# esp32wrom.net
KiCad netlist of a schematic drawn in Altium Designer
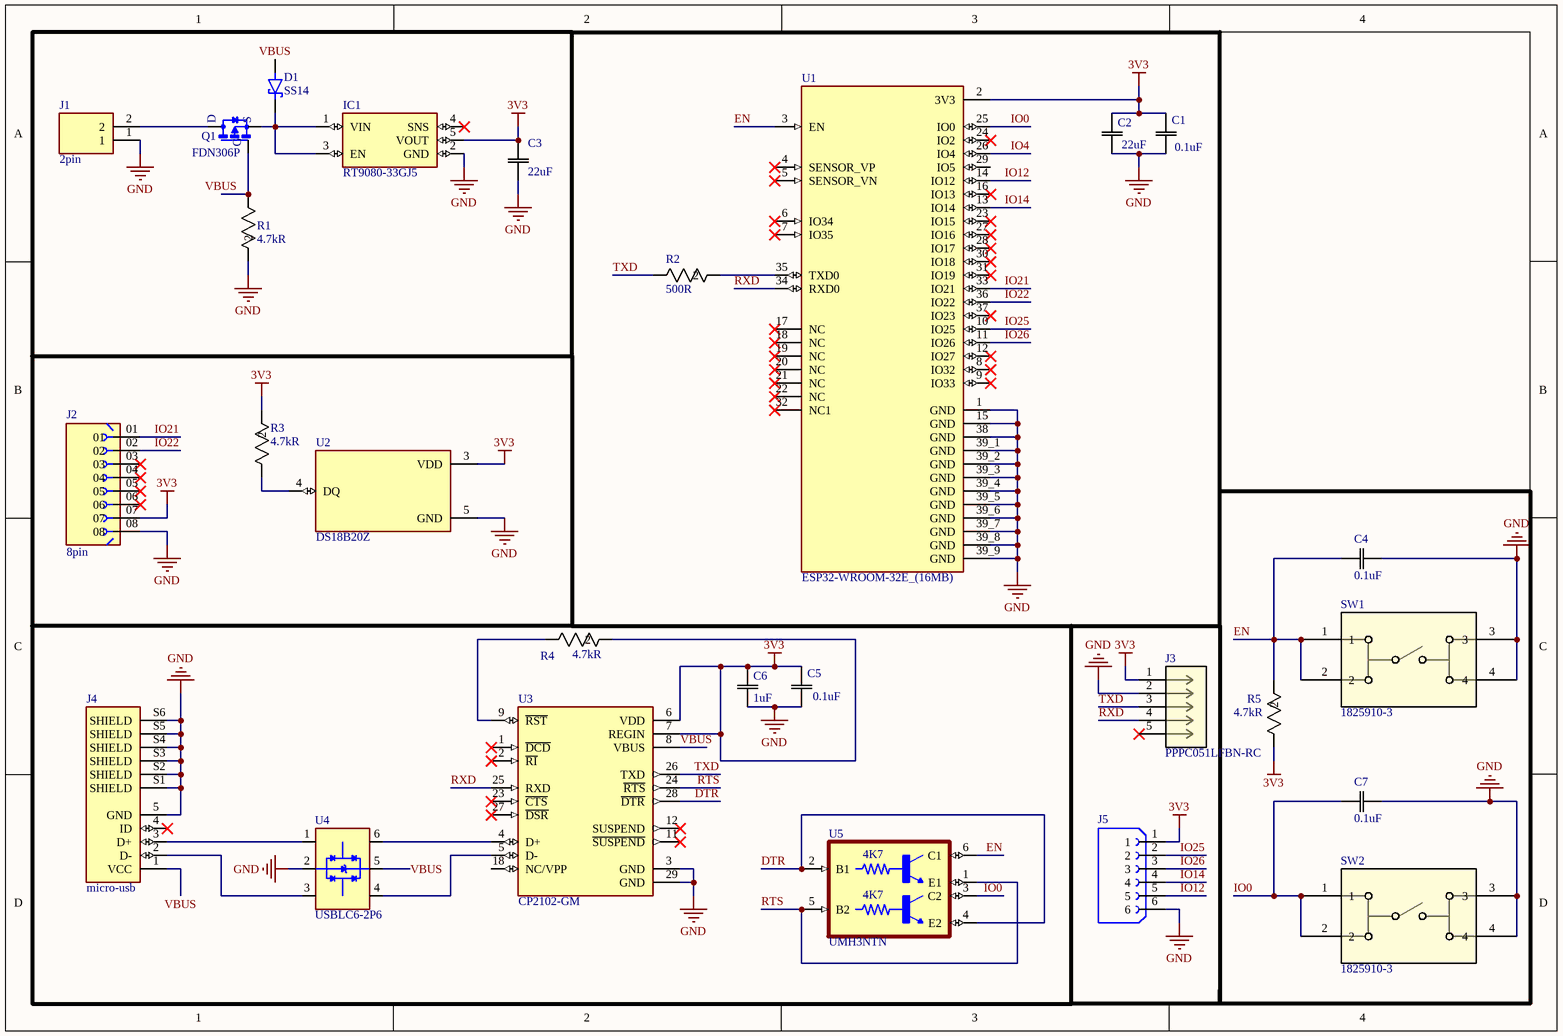
[diagram p0: esp32wrom.SchDoc]

(export (version "E")
  (design (tool "Eeschema 10.0.6"))
  (components
    (comp (ref "C1")
      (value "0.1uF")
      (footprint "0603_AVX")
      (description "Description")
      (fields
        (field (name "MANUFACTURER_PART_NUMBER") "0603YC683KAT2A")
        (field (name "COPYRIGHT") "Copyright (C) 2025 Ultra Librarian. All rights reserved.")
      )
      (libsource (lib "capacitor") (part "0603"))
    )
    (comp (ref "C2")
      (value "22uF")
      (footprint "0603_AVX")
      (description "Description")
      (fields
        (field (name "MANUFACTURER_PART_NUMBER") "0603YC683KAT2A")
        (field (name "COPYRIGHT") "Copyright (C) 2025 Ultra Librarian. All rights reserved.")
      )
      (libsource (lib "capacitor") (part "0603"))
    )
    (comp (ref "C3")
      (value "22uF")
      (footprint "0603_AVX")
      (description "Description")
      (fields
        (field (name "MANUFACTURER_PART_NUMBER") "0603YC683KAT2A")
        (field (name "COPYRIGHT") "Copyright (C) 2025 Ultra Librarian. All rights reserved.")
      )
      (libsource (lib "capacitor") (part "0603"))
    )
    (comp (ref "C4")
      (value "0.1uF")
      (footprint "0603_AVX")
      (description "Description")
      (fields
        (field (name "MANUFACTURER_PART_NUMBER") "0603YC683KAT2A")
        (field (name "COPYRIGHT") "Copyright (C) 2025 Ultra Librarian. All rights reserved.")
      )
      (libsource (lib "capacitor") (part "0603"))
    )
    (comp (ref "C5")
      (value "0.1uF")
      (footprint "0603_AVX")
      (description "Description")
      (fields
        (field (name "MANUFACTURER_PART_NUMBER") "0603YC683KAT2A")
        (field (name "COPYRIGHT") "Copyright (C) 2025 Ultra Librarian. All rights reserved.")
      )
      (libsource (lib "capacitor") (part "0603"))
    )
    (comp (ref "C6")
      (value "1uF")
      (footprint "0603_AVX")
      (description "Description")
      (fields
        (field (name "MANUFACTURER_PART_NUMBER") "0603YC683KAT2A")
        (field (name "COPYRIGHT") "Copyright (C) 2025 Ultra Librarian. All rights reserved.")
      )
      (libsource (lib "capacitor") (part "0603"))
    )
    (comp (ref "C7")
      (value "0.1uF")
      (footprint "0603_AVX")
      (description "Description")
      (fields
        (field (name "MANUFACTURER_PART_NUMBER") "0603YC683KAT2A")
        (field (name "COPYRIGHT") "Copyright (C) 2025 Ultra Librarian. All rights reserved.")
      )
      (libsource (lib "capacitor") (part "0603"))
    )
    (comp (ref "D1")
      (value "SS14")
      (footprint "DIOM4325X250N")
      (description "1A, 40V, Schottky Rectifier")
      (fields (field (name "MF") "Taiwan Semiconductor"))
      (libsource (lib "stm32_Wrom") (part "SS14"))
    )
    (comp (ref "IC1")
      (value "RT9080-33GJ5")
      (footprint "SOT94P280X100-5N")
      (description "Linear Voltage Regulator IC Positive Fixed 1 Output 600mA TSOT-23-5")
      (fields (field (name "MF") "Richtek USA"))
      (libsource (lib "stm32_Wrom") (part "RT9080-33GJ5"))
    )
    (comp (ref "J1")
      (value "2pin")
      (footprint "JST_S2B-PH-K-S(LF)(SN)")
      (description "Connector Header Through Hole, Right Angle 2 position")
      (fields (field (name "MP") "S2B-PH-K-S(LF)(SN)") (field (name "MF") "JST Sales America Inc."))
      (libsource (lib "stm32_Wrom") (part "2pin"))
    )
    (comp (ref "J2")
      (value "8pin")
      (footprint "AMPHENOL_76308-108LF")
      (fields (field (name "MP") "76308-108LF") (field (name "MF") "Amphenol"))
      (libsource (lib "stm32_Wrom") (part "8pin"))
    )
    (comp (ref "J3")
      (value "PPPC051LFBN-RC")
      (footprint "CONN_PPPC051LFBN-RC_SUL")
      (description "Description")
      (fields (field (name "COPYRIGHT") "Copyright (C) 2025 Ultra Librarian. All rights reserved."))
      (libsource (lib "stm32_Wrom") (part "5pin"))
    )
    (comp (ref "J4")
      (value "micro-usb")
      (footprint "AMPHENOL_10118192-0002LF")
      (description "Micro USB 2.0, Input Output Connectors, B TYPE RECEPTACLE without flange")
      (fields (field (name "MF") "Amphenol ICC") (field (name "MP") "10118192-0002LF"))
      (libsource (lib "stm32_Wrom") (part "micro-usb"))
    )
    (comp (ref "J5")
      (value "6pin")
      (footprint "SULLINS_PPTC061LFBN-RC")
      (description "6 Position Total Single Row 2.54 mm Pitch Straight Female Header")
      (fields (field (name "MF") "Sullins Connector Solutions") (field (name "MP") "PPTC061LFBNRC"))
      (libsource (lib "stm32_Wrom") (part "6pin"))
    )
    (comp (ref "Q1")
      (value "FDN306P")
      (footprint "SSOT-3")
      (description "P-Channel 12V 2.6A (Ta) 500mW (Ta) Surface Mount SuperSOT-3")
      (fields (field (name "MF") "ON Semiconductor"))
      (libsource (lib "stm32_Wrom") (part "FDN306P"))
    )
    (comp (ref "R1")
      (value "4.7kR")
      (footprint "RC0603N_PAN")
      (description "No Description Available")
      (fields
        (field (name "MANUFACTURER_PART_NUMBER") "ERJ-3GEYJ6R8V")
        (field (name "COPYRIGHT") "Copyright (C) 2025 Ultra Librarian. All rights reserved.")
      )
      (libsource (lib "resistor") (part "0603"))
    )
    (comp (ref "R2")
      (value "500R")
      (footprint "RC0603N_PAN")
      (description "No Description Available")
      (fields
        (field (name "MANUFACTURER_PART_NUMBER") "ERJ-3GEYJ6R8V")
        (field (name "COPYRIGHT") "Copyright (C) 2025 Ultra Librarian. All rights reserved.")
      )
      (libsource (lib "resistor") (part "0603"))
    )
    (comp (ref "R3")
      (value "4.7kR")
      (footprint "RC0603N_PAN")
      (description "No Description Available")
      (fields
        (field (name "MANUFACTURER_PART_NUMBER") "ERJ-3GEYJ6R8V")
        (field (name "COPYRIGHT") "Copyright (C) 2025 Ultra Librarian. All rights reserved.")
      )
      (libsource (lib "resistor") (part "0603"))
    )
    (comp (ref "R4")
      (value "4.7kR")
      (footprint "RC0603N_PAN")
      (description "No Description Available")
      (fields
        (field (name "MANUFACTURER_PART_NUMBER") "ERJ-3GEYJ6R8V")
        (field (name "COPYRIGHT") "Copyright (C) 2025 Ultra Librarian. All rights reserved.")
      )
      (libsource (lib "resistor") (part "0603"))
    )
    (comp (ref "R5")
      (value "4.7kR")
      (footprint "RC0603N_PAN")
      (description "No Description Available")
      (fields
        (field (name "MANUFACTURER_PART_NUMBER") "ERJ-3GEYJ6R8V")
        (field (name "COPYRIGHT") "Copyright (C) 2025 Ultra Librarian. All rights reserved.")
      )
      (libsource (lib "resistor") (part "0603"))
    )
    (comp (ref "SW1")
      (value "1825910-3")
      (footprint "SW4_1825910-A_TEC")
      (description "FSM2JAH=6MM TACT SWITCH, HIGH TEMP")
      (fields (field (name "COPYRIGHT") "Copyright (C) 2025 Ultra Librarian. All rights reserved."))
      (libsource (lib "stm32_Wrom") (part "1825910-3"))
    )
    (comp (ref "SW2")
      (value "1825910-3")
      (footprint "SW4_1825910-A_TEC")
      (description "FSM2JAH=6MM TACT SWITCH, HIGH TEMP")
      (fields (field (name "COPYRIGHT") "Copyright (C) 2025 Ultra Librarian. All rights reserved."))
      (libsource (lib "stm32_Wrom") (part "1825910-3"))
    )
    (comp (ref "U1")
      (value "ESP32-WROOM-32E_(16MB)")
      (footprint "XCVR_ESP32-WROOM-32E_(16MB)")
      (fields (field (name "MP") "ESP32-WROOM-32E (16MB)") (field (name "MF") "Espressif Systems"))
      (libsource (lib "stm32_Wrom") (part "ESP32-WROOM-32E_(16MB)"))
    )
    (comp (ref "U2")
      (value "DS18B20Z")
      (footprint "SOIC127P600X175-8N")
      (description "Programmable Resolution 1-Wire Digital Thermometer")
      (fields (field (name "MF") "Analog Devices") (field (name "MP") "DS18B20Z+T&amp;R"))
      (libsource (lib "stm32_Wrom") (part "DS18B20Z"))
    )
    (comp (ref "U3")
      (value "CP2102-GM")
      (footprint "QFN50P500X500X100-29N")
      (description "USB Bridge, USB to UART USB 2.0 UART Interface 28-QFN (5x5)")
      (fields (field (name "MF") "Silicon Labs"))
      (libsource (lib "stm32_Wrom") (part "CP2102-GM"))
    )
    (comp (ref "U4")
      (value "USBLC6-2P6")
      (footprint "SOT50P160X60-6N")
      (description "17V Clamp 5A (8/20Âµs) Ipp Tvs Diode Surface Mount SOT-666")
      (fields (field (name "MF") "STMicroelectronics"))
      (libsource (lib "stm32_Wrom") (part "USBLC6-2P6"))
    )
    (comp (ref "U5")
      (value "UMH3NTN")
      (footprint "SOP65P210X100-6N")
      (fields (field (name "MF") "Rohm"))
      (libsource (lib "stm32_Wrom") (part "UMH3NTN"))
    )
  )
  (nets
    (net (code "1") (name "/DTR") (class "Default")
      (node (ref "U3") (pin "28") (pinfunction "~{DTR}_28") (pintype "output"))
      (node (ref "U5") (pin "2") (pinfunction "B1_2") (pintype "input"))
      (node (ref "U5") (pin "4") (pinfunction "E2_4") (pintype "bidirectional"))
    )
    (net (code "2") (name "/EN") (class "Default")
      (node (ref "C4") (pin "2") (pinfunction "2_2") (pintype "passive"))
      (node (ref "R5") (pin "2") (pinfunction "2_2") (pintype "passive"))
      (node (ref "SW1") (pin "1") (pinfunction "1_1") (pintype "passive"))
      (node (ref "SW1") (pin "2") (pinfunction "2_2") (pintype "passive"))
      (node (ref "U1") (pin "3") (pinfunction "EN_3") (pintype "input"))
      (node (ref "U5") (pin "6") (pinfunction "C1_6") (pintype "bidirectional"))
    )
    (net (code "3") (name "/IO0") (class "Default")
      (node (ref "C7") (pin "2") (pinfunction "2_2") (pintype "passive"))
      (node (ref "SW2") (pin "1") (pinfunction "1_1") (pintype "passive"))
      (node (ref "SW2") (pin "2") (pinfunction "2_2") (pintype "passive"))
      (node (ref "U1") (pin "25") (pinfunction "IO0_25") (pintype "bidirectional"))
      (node (ref "U5") (pin "3") (pinfunction "C2_3") (pintype "bidirectional"))
    )
    (net (code "4") (name "/IO4") (class "Default")
      (node (ref "U1") (pin "26") (pinfunction "IO4_26") (pintype "bidirectional"))
    )
    (net (code "5") (name "/IO12") (class "Default")
      (node (ref "J5") (pin "5") (pinfunction "5_5") (pintype "passive"))
      (node (ref "U1") (pin "14") (pinfunction "IO12_14") (pintype "bidirectional"))
    )
    (net (code "6") (name "/IO14") (class "Default")
      (node (ref "J5") (pin "4") (pinfunction "4_4") (pintype "passive"))
      (node (ref "U1") (pin "13") (pinfunction "IO14_13") (pintype "bidirectional"))
    )
    (net (code "7") (name "/IO21") (class "Default")
      (node (ref "J2") (pin "01") (pinfunction "01_01") (pintype "passive"))
      (node (ref "U1") (pin "33") (pinfunction "IO21_33") (pintype "bidirectional"))
    )
    (net (code "8") (name "/IO22") (class "Default")
      (node (ref "J2") (pin "02") (pinfunction "02_02") (pintype "passive"))
      (node (ref "U1") (pin "36") (pinfunction "IO22_36") (pintype "bidirectional"))
    )
    (net (code "9") (name "/IO25") (class "Default")
      (node (ref "J5") (pin "2") (pinfunction "2_2") (pintype "passive"))
      (node (ref "U1") (pin "10") (pinfunction "IO25_10") (pintype "bidirectional"))
    )
    (net (code "10") (name "/IO26") (class "Default")
      (node (ref "J5") (pin "3") (pinfunction "3_3") (pintype "passive"))
      (node (ref "U1") (pin "11") (pinfunction "IO26_11") (pintype "bidirectional"))
    )
    (net (code "11") (name "/RTS") (class "Default")
      (node (ref "U3") (pin "24") (pinfunction "~{RTS}_24") (pintype "output"))
      (node (ref "U5") (pin "1") (pinfunction "E1_1") (pintype "bidirectional"))
      (node (ref "U5") (pin "5") (pinfunction "B2_5") (pintype "input"))
    )
    (net (code "12") (name "/RXD") (class "Default")
      (node (ref "J3") (pin "4") (pinfunction "4_4") (pintype "passive"))
      (node (ref "U1") (pin "34") (pinfunction "RXD0_34") (pintype "bidirectional"))
      (node (ref "U3") (pin "25") (pinfunction "RXD_25") (pintype "input"))
    )
    (net (code "13") (name "/TXD") (class "Default")
      (node (ref "J3") (pin "3") (pinfunction "3_3") (pintype "passive"))
      (node (ref "R2") (pin "1") (pinfunction "1_1") (pintype "passive"))
      (node (ref "U3") (pin "26") (pinfunction "TXD_26") (pintype "output"))
    )
    (net (code "14") (name "/VBUS") (class "Default")
      (node (ref "D1") (pin "A") (pinfunction "A_A") (pintype "passive"))
      (node (ref "J4") (pin "1") (pinfunction "VCC_1") (pintype "power_in"))
      (node (ref "Q1") (pin "1") (pinfunction "G_1") (pintype "passive"))
      (node (ref "R1") (pin "1") (pinfunction "1_1") (pintype "passive"))
      (node (ref "U3") (pin "8") (pinfunction "VBUS_8") (pintype "power_in"))
      (node (ref "U4") (pin "5") (pinfunction "VBUS_5") (pintype "power_in"))
    )
    (net (code "15") (name "3V3") (class "Default")
      (node (ref "C1") (pin "2") (pinfunction "2_2") (pintype "passive"))
      (node (ref "C2") (pin "2") (pinfunction "2_2") (pintype "passive"))
      (node (ref "C3") (pin "2") (pinfunction "2_2") (pintype "passive"))
      (node (ref "C5") (pin "2") (pinfunction "2_2") (pintype "passive"))
      (node (ref "C6") (pin "2") (pinfunction "2_2") (pintype "passive"))
      (node (ref "IC1") (pin "5") (pinfunction "VOUT_5") (pintype "bidirectional"))
      (node (ref "J2") (pin "07") (pinfunction "07_07") (pintype "passive"))
      (node (ref "J3") (pin "1") (pinfunction "1_1") (pintype "passive"))
      (node (ref "J5") (pin "1") (pinfunction "1_1") (pintype "passive"))
      (node (ref "R3") (pin "2") (pinfunction "2_2") (pintype "passive"))
      (node (ref "R4") (pin "2") (pinfunction "2_2") (pintype "passive"))
      (node (ref "R5") (pin "1") (pinfunction "1_1") (pintype "passive"))
      (node (ref "U1") (pin "2") (pinfunction "3V3_2") (pintype "power_in"))
      (node (ref "U2") (pin "3") (pinfunction "VDD_3") (pintype "power_in"))
      (node (ref "U3") (pin "6") (pinfunction "VDD_6") (pintype "power_in"))
      (node (ref "U3") (pin "7") (pinfunction "REGIN_7") (pintype "power_in"))
    )
    (net (code "16") (name "GND") (class "Default")
      (node (ref "C1") (pin "1") (pinfunction "1_1") (pintype "passive"))
      (node (ref "C2") (pin "1") (pinfunction "1_1") (pintype "passive"))
      (node (ref "C3") (pin "1") (pinfunction "1_1") (pintype "passive"))
      (node (ref "C4") (pin "1") (pinfunction "1_1") (pintype "passive"))
      (node (ref "C5") (pin "1") (pinfunction "1_1") (pintype "passive"))
      (node (ref "C6") (pin "1") (pinfunction "1_1") (pintype "passive"))
      (node (ref "C7") (pin "1") (pinfunction "1_1") (pintype "passive"))
      (node (ref "IC1") (pin "2") (pinfunction "GND_2") (pintype "bidirectional"))
      (node (ref "J1") (pin "1") (pinfunction "1_1") (pintype "passive"))
      (node (ref "J2") (pin "08") (pinfunction "08_08") (pintype "passive"))
      (node (ref "J3") (pin "2") (pinfunction "2_2") (pintype "passive"))
      (node (ref "J4") (pin "5") (pinfunction "GND_5") (pintype "power_in"))
      (node (ref "J4") (pin "S1") (pinfunction "SHIELD_S1") (pintype "passive"))
      (node (ref "J4") (pin "S2") (pinfunction "SHIELD_S2") (pintype "passive"))
      (node (ref "J4") (pin "S3") (pinfunction "SHIELD_S3") (pintype "passive"))
      (node (ref "J4") (pin "S4") (pinfunction "SHIELD_S4") (pintype "passive"))
      (node (ref "J4") (pin "S5") (pinfunction "SHIELD_S5") (pintype "passive"))
      (node (ref "J4") (pin "S6") (pinfunction "SHIELD_S6") (pintype "passive"))
      (node (ref "J5") (pin "6") (pinfunction "6_6") (pintype "passive"))
      (node (ref "R1") (pin "2") (pinfunction "2_2") (pintype "passive"))
      (node (ref "SW1") (pin "3") (pinfunction "3_3") (pintype "passive"))
      (node (ref "SW1") (pin "4") (pinfunction "4_4") (pintype "passive"))
      (node (ref "SW2") (pin "3") (pinfunction "3_3") (pintype "passive"))
      (node (ref "SW2") (pin "4") (pinfunction "4_4") (pintype "passive"))
      (node (ref "U1") (pin "1") (pinfunction "GND_1") (pintype "power_in"))
      (node (ref "U1") (pin "15") (pinfunction "GND_15") (pintype "power_in"))
      (node (ref "U1") (pin "38") (pinfunction "GND_38") (pintype "power_in"))
      (node (ref "U1") (pin "39_1") (pinfunction "GND_39_1") (pintype "power_in"))
      (node (ref "U1") (pin "39_2") (pinfunction "GND_39_2") (pintype "power_in"))
      (node (ref "U1") (pin "39_3") (pinfunction "GND_39_3") (pintype "power_in"))
      (node (ref "U1") (pin "39_4") (pinfunction "GND_39_4") (pintype "power_in"))
      (node (ref "U1") (pin "39_5") (pinfunction "GND_39_5") (pintype "power_in"))
      (node (ref "U1") (pin "39_6") (pinfunction "GND_39_6") (pintype "power_in"))
      (node (ref "U1") (pin "39_7") (pinfunction "GND_39_7") (pintype "power_in"))
      (node (ref "U1") (pin "39_8") (pinfunction "GND_39_8") (pintype "power_in"))
      (node (ref "U1") (pin "39_9") (pinfunction "GND_39_9") (pintype "power_in"))
      (node (ref "U2") (pin "5") (pinfunction "GND_5") (pintype "power_in"))
      (node (ref "U3") (pin "29") (pinfunction "GND_29") (pintype "power_in"))
      (node (ref "U3") (pin "3") (pinfunction "GND_3") (pintype "power_in"))
      (node (ref "U4") (pin "2") (pinfunction "GND_2") (pintype "power_in"))
    )
    (net (code "17") (name "Net-(D1-K)") (class "Default")
      (node (ref "D1") (pin "C") (pinfunction "K_C") (pintype "passive"))
      (node (ref "IC1") (pin "1") (pinfunction "VIN_1") (pintype "bidirectional"))
      (node (ref "IC1") (pin "3") (pinfunction "EN_3") (pintype "bidirectional"))
      (node (ref "Q1") (pin "2") (pinfunction "S_2") (pintype "passive"))
    )
    (net (code "18") (name "Net-(J4-D+)") (class "Default")
      (node (ref "J4") (pin "3") (pinfunction "D+_3") (pintype "bidirectional"))
      (node (ref "U4") (pin "1") (pinfunction "I/O1_1_1") (pintype "bidirectional"))
    )
    (net (code "19") (name "Net-(J4-D-)") (class "Default")
      (node (ref "J4") (pin "2") (pinfunction "D-_2") (pintype "bidirectional"))
      (node (ref "U4") (pin "3") (pinfunction "I/O2_1_3") (pintype "bidirectional"))
    )
    (net (code "20") (name "Net-(Q1-D)") (class "Default")
      (node (ref "J1") (pin "2") (pinfunction "2_2") (pintype "passive"))
      (node (ref "Q1") (pin "3") (pinfunction "D_3") (pintype "passive"))
    )
    (net (code "21") (name "Net-(U1-TXD0)") (class "Default")
      (node (ref "R2") (pin "2") (pinfunction "2_2") (pintype "passive"))
      (node (ref "U1") (pin "35") (pinfunction "TXD0_35") (pintype "bidirectional"))
    )
    (net (code "22") (name "Net-(U2-DQ)") (class "Default")
      (node (ref "R3") (pin "1") (pinfunction "1_1") (pintype "passive"))
      (node (ref "U2") (pin "4") (pinfunction "DQ_4") (pintype "bidirectional"))
    )
    (net (code "23") (name "Net-(U3-D+)") (class "Default")
      (node (ref "U3") (pin "4") (pinfunction "D+_4") (pintype "bidirectional"))
      (node (ref "U4") (pin "6") (pinfunction "I/O1_2_6") (pintype "bidirectional"))
    )
    (net (code "24") (name "Net-(U3-D-)") (class "Default")
      (node (ref "U3") (pin "5") (pinfunction "D-_5") (pintype "bidirectional"))
      (node (ref "U4") (pin "4") (pinfunction "I/O2_2_4") (pintype "bidirectional"))
    )
    (net (code "25") (name "Net-(U3-~{RST})") (class "Default")
      (node (ref "R4") (pin "1") (pinfunction "1_1") (pintype "passive"))
      (node (ref "U3") (pin "9") (pinfunction "~{RST}_9") (pintype "bidirectional"))
    )
    (net (code "26") (name "unconnected-(IC1-SNS-Pad4)") (class "Default")
      (node (ref "IC1") (pin "4") (pinfunction "SNS_4") (pintype "bidirectional+no_connect"))
    )
    (net (code "27") (name "unconnected-(J2-Pad03)") (class "Default")
      (node (ref "J2") (pin "03") (pinfunction "03_03") (pintype "passive+no_connect"))
    )
    (net (code "28") (name "unconnected-(J2-Pad04)") (class "Default")
      (node (ref "J2") (pin "04") (pinfunction "04_04") (pintype "passive+no_connect"))
    )
    (net (code "29") (name "unconnected-(J2-Pad05)") (class "Default")
      (node (ref "J2") (pin "05") (pinfunction "05_05") (pintype "passive+no_connect"))
    )
    (net (code "30") (name "unconnected-(J2-Pad06)") (class "Default")
      (node (ref "J2") (pin "06") (pinfunction "06_06") (pintype "passive+no_connect"))
    )
    (net (code "31") (name "unconnected-(J3-Pad5)") (class "Default")
      (node (ref "J3") (pin "5") (pinfunction "5_5") (pintype "passive+no_connect"))
    )
    (net (code "32") (name "unconnected-(J4-ID-Pad4)") (class "Default")
      (node (ref "J4") (pin "4") (pinfunction "ID_4") (pintype "bidirectional+no_connect"))
    )
    (net (code "33") (name "unconnected-(U1-IO2-Pad24)") (class "Default")
      (node (ref "U1") (pin "24") (pinfunction "IO2_24") (pintype "bidirectional+no_connect"))
    )
    (net (code "34") (name "unconnected-(U1-IO5-Pad29)") (class "Default")
      (node (ref "U1") (pin "29") (pinfunction "IO5_29") (pintype "bidirectional"))
    )
    (net (code "35") (name "unconnected-(U1-IO13-Pad16)") (class "Default")
      (node (ref "U1") (pin "16") (pinfunction "IO13_16") (pintype "bidirectional+no_connect"))
    )
    (net (code "36") (name "unconnected-(U1-IO15-Pad23)") (class "Default")
      (node (ref "U1") (pin "23") (pinfunction "IO15_23") (pintype "bidirectional+no_connect"))
    )
    (net (code "37") (name "unconnected-(U1-IO16-Pad27)") (class "Default")
      (node (ref "U1") (pin "27") (pinfunction "IO16_27") (pintype "bidirectional+no_connect"))
    )
    (net (code "38") (name "unconnected-(U1-IO17-Pad28)") (class "Default")
      (node (ref "U1") (pin "28") (pinfunction "IO17_28") (pintype "bidirectional+no_connect"))
    )
    (net (code "39") (name "unconnected-(U1-IO18-Pad30)") (class "Default")
      (node (ref "U1") (pin "30") (pinfunction "IO18_30") (pintype "bidirectional+no_connect"))
    )
    (net (code "40") (name "unconnected-(U1-IO19-Pad31)") (class "Default")
      (node (ref "U1") (pin "31") (pinfunction "IO19_31") (pintype "bidirectional+no_connect"))
    )
    (net (code "41") (name "unconnected-(U1-IO23-Pad37)") (class "Default")
      (node (ref "U1") (pin "37") (pinfunction "IO23_37") (pintype "bidirectional+no_connect"))
    )
    (net (code "42") (name "unconnected-(U1-IO27-Pad12)") (class "Default")
      (node (ref "U1") (pin "12") (pinfunction "IO27_12") (pintype "bidirectional+no_connect"))
    )
    (net (code "43") (name "unconnected-(U1-IO32-Pad8)") (class "Default")
      (node (ref "U1") (pin "8") (pinfunction "IO32_8") (pintype "bidirectional+no_connect"))
    )
    (net (code "44") (name "unconnected-(U1-IO33-Pad9)") (class "Default")
      (node (ref "U1") (pin "9") (pinfunction "IO33_9") (pintype "bidirectional+no_connect"))
    )
    (net (code "45") (name "unconnected-(U1-IO34-Pad6)") (class "Default")
      (node (ref "U1") (pin "6") (pinfunction "IO34_6") (pintype "input+no_connect"))
    )
    (net (code "46") (name "unconnected-(U1-IO35-Pad7)") (class "Default")
      (node (ref "U1") (pin "7") (pinfunction "IO35_7") (pintype "input+no_connect"))
    )
    (net (code "47") (name "unconnected-(U1-NC-Pad17)") (class "Default")
      (node (ref "U1") (pin "17") (pinfunction "NC_17") (pintype "passive+no_connect"))
    )
    (net (code "48") (name "unconnected-(U1-NC-Pad18)") (class "Default")
      (node (ref "U1") (pin "18") (pinfunction "NC_18") (pintype "passive+no_connect"))
    )
    (net (code "49") (name "unconnected-(U1-NC-Pad19)") (class "Default")
      (node (ref "U1") (pin "19") (pinfunction "NC_19") (pintype "passive+no_connect"))
    )
    (net (code "50") (name "unconnected-(U1-NC-Pad20)") (class "Default")
      (node (ref "U1") (pin "20") (pinfunction "NC_20") (pintype "passive+no_connect"))
    )
    (net (code "51") (name "unconnected-(U1-NC-Pad21)") (class "Default")
      (node (ref "U1") (pin "21") (pinfunction "NC_21") (pintype "passive+no_connect"))
    )
    (net (code "52") (name "unconnected-(U1-NC-Pad22)") (class "Default")
      (node (ref "U1") (pin "22") (pinfunction "NC_22") (pintype "passive+no_connect"))
    )
    (net (code "53") (name "unconnected-(U1-NC1-Pad32)") (class "Default")
      (node (ref "U1") (pin "32") (pinfunction "NC1_32") (pintype "passive+no_connect"))
    )
    (net (code "54") (name "unconnected-(U1-SENSOR_VN-Pad5)") (class "Default")
      (node (ref "U1") (pin "5") (pinfunction "SENSOR_VN_5") (pintype "input+no_connect"))
    )
    (net (code "55") (name "unconnected-(U1-SENSOR_VP-Pad4)") (class "Default")
      (node (ref "U1") (pin "4") (pinfunction "SENSOR_VP_4") (pintype "input+no_connect"))
    )
    (net (code "56") (name "unconnected-(U3-NC{slash}VPP-Pad18)") (class "Default")
      (node (ref "U3") (pin "18") (pinfunction "NC/VPP_18") (pintype "bidirectional"))
    )
    (net (code "57") (name "unconnected-(U3-SUSPEND-Pad12)") (class "Default")
      (node (ref "U3") (pin "12") (pinfunction "SUSPEND_12") (pintype "output+no_connect"))
    )
    (net (code "58") (name "unconnected-(U3-~{CTS}-Pad23)") (class "Default")
      (node (ref "U3") (pin "23") (pinfunction "~{CTS}_23") (pintype "input+no_connect"))
    )
    (net (code "59") (name "unconnected-(U3-~{DCD}-Pad1)") (class "Default")
      (node (ref "U3") (pin "1") (pinfunction "~{DCD}_1") (pintype "input+no_connect"))
    )
    (net (code "60") (name "unconnected-(U3-~{DSR}-Pad27)") (class "Default")
      (node (ref "U3") (pin "27") (pinfunction "~{DSR}_27") (pintype "input+no_connect"))
    )
    (net (code "61") (name "unconnected-(U3-~{RI}-Pad2)") (class "Default")
      (node (ref "U3") (pin "2") (pinfunction "~{RI}_2") (pintype "input+no_connect"))
    )
    (net (code "62") (name "unconnected-(U3-~{SUSPEND}-Pad11)") (class "Default")
      (node (ref "U3") (pin "11") (pinfunction "~{SUSPEND}_11") (pintype "output+no_connect"))
    )
  )
)
